# STM32.net
KiCad netlist of a schematic drawn in Altium Designer
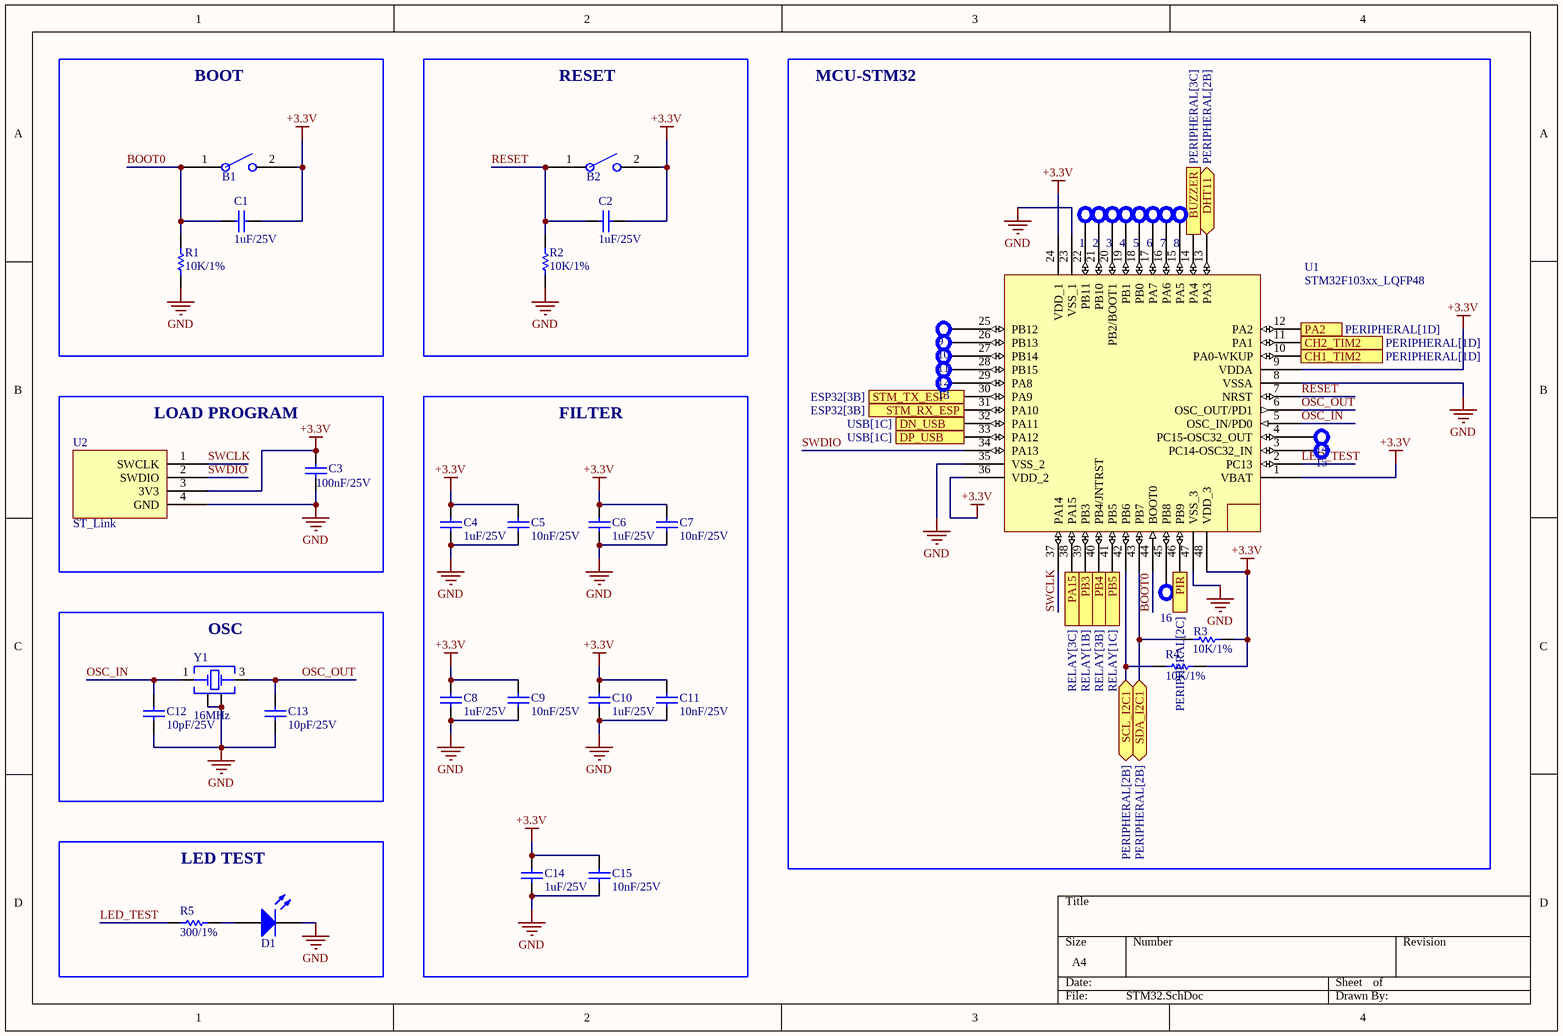
[diagram p0: STM32.SchDoc]

(export (version "E")
  (design (tool "Eeschema 10.0.6"))
  (components
    (comp (ref "1")
      (value "Test Point")
      (footprint "TP")
      (libsource (lib "Giang's Libs") (part "Test Point"))
    )
    (comp (ref "2")
      (value "Test Point")
      (footprint "TP")
      (libsource (lib "Giang's Libs") (part "Test Point"))
    )
    (comp (ref "3")
      (value "Test Point")
      (footprint "TP")
      (libsource (lib "Giang's Libs") (part "Test Point"))
    )
    (comp (ref "4")
      (value "Test Point")
      (footprint "TP")
      (libsource (lib "Giang's Libs") (part "Test Point"))
    )
    (comp (ref "5")
      (value "Test Point")
      (footprint "TP")
      (libsource (lib "Giang's Libs") (part "Test Point"))
    )
    (comp (ref "6")
      (value "Test Point")
      (footprint "TP")
      (libsource (lib "Giang's Libs") (part "Test Point"))
    )
    (comp (ref "7")
      (value "Test Point")
      (footprint "TP")
      (libsource (lib "Giang's Libs") (part "Test Point"))
    )
    (comp (ref "8")
      (value "Test Point")
      (footprint "TP")
      (libsource (lib "Giang's Libs") (part "Test Point"))
    )
    (comp (ref "9")
      (value "Test Point")
      (footprint "TP")
      (libsource (lib "Giang's Libs") (part "Test Point"))
    )
    (comp (ref "10")
      (value "Test Point")
      (footprint "TP")
      (libsource (lib "Giang's Libs") (part "Test Point"))
    )
    (comp (ref "11")
      (value "Test Point")
      (footprint "TP")
      (libsource (lib "Giang's Libs") (part "Test Point"))
    )
    (comp (ref "12")
      (value "Test Point")
      (footprint "TP")
      (libsource (lib "Giang's Libs") (part "Test Point"))
    )
    (comp (ref "13")
      (value "Test Point")
      (footprint "TP")
      (libsource (lib "Giang's Libs") (part "Test Point"))
    )
    (comp (ref "14")
      (value "Test Point")
      (footprint "TP")
      (libsource (lib "Giang's Libs") (part "Test Point"))
    )
    (comp (ref "15")
      (value "Test Point")
      (footprint "TP")
      (libsource (lib "Giang's Libs") (part "Test Point"))
    )
    (comp (ref "16")
      (value "Test Point")
      (footprint "TP")
      (libsource (lib "Giang's Libs") (part "Test Point"))
    )
    (comp (ref "B1")
      (value "Button SMD 2 Pin 3x4mm")
      (footprint "BUTTON SMD 2 PIN")
      (libsource (lib "Libs_NGOCCAM") (part "BUTTON"))
    )
    (comp (ref "B2")
      (value "Button SMD 2 Pin 3x4mm")
      (footprint "BUTTON SMD 2 PIN")
      (libsource (lib "Libs_NGOCCAM") (part "BUTTON"))
    )
    (comp (ref "C1")
      (value "1uF/25V")
      (footprint "CAP-SM-0805")
      (description "Capacitor")
      (fields (field (name "Comment") "Cap Non-Pol SMD"))
      (libsource (lib "PIF_Library") (part "Cap Non-Pol SMD"))
    )
    (comp (ref "C2")
      (value "1uF/25V")
      (footprint "CAP-SM-0805")
      (description "Capacitor")
      (fields (field (name "Comment") "Cap Non-Pol SMD"))
      (libsource (lib "PIF_Library") (part "Cap Non-Pol SMD"))
    )
    (comp (ref "C3")
      (value "100nF/25V")
      (footprint "CAP-SM-0805")
      (description "Capacitor")
      (fields (field (name "Comment") "Cap Non-Pol SMD"))
      (libsource (lib "PIF_Library") (part "Cap Non-Pol SMD"))
    )
    (comp (ref "C4")
      (value "1uF/25V")
      (footprint "CAP-SM-0805")
      (description "Capacitor")
      (fields (field (name "Comment") "Cap Non-Pol SMD"))
      (libsource (lib "PIF_Library") (part "Cap Non-Pol SMD"))
    )
    (comp (ref "C5")
      (value "10nF/25V")
      (footprint "CAP-SM-0805")
      (description "Capacitor")
      (fields (field (name "Comment") "Cap Non-Pol SMD"))
      (libsource (lib "PIF_Library") (part "Cap Non-Pol SMD"))
    )
    (comp (ref "C6")
      (value "1uF/25V")
      (footprint "CAP-SM-0805")
      (description "Capacitor")
      (fields (field (name "Comment") "Cap Non-Pol SMD"))
      (libsource (lib "PIF_Library") (part "Cap Non-Pol SMD"))
    )
    (comp (ref "C7")
      (value "10nF/25V")
      (footprint "CAP-SM-0805")
      (description "Capacitor")
      (fields (field (name "Comment") "Cap Non-Pol SMD"))
      (libsource (lib "PIF_Library") (part "Cap Non-Pol SMD"))
    )
    (comp (ref "C8")
      (value "1uF/25V")
      (footprint "CAP-SM-0805")
      (description "Capacitor")
      (fields (field (name "Comment") "Cap Non-Pol SMD"))
      (libsource (lib "PIF_Library") (part "Cap Non-Pol SMD"))
    )
    (comp (ref "C9")
      (value "10nF/25V")
      (footprint "CAP-SM-0805")
      (description "Capacitor")
      (fields (field (name "Comment") "Cap Non-Pol SMD"))
      (libsource (lib "PIF_Library") (part "Cap Non-Pol SMD"))
    )
    (comp (ref "C10")
      (value "1uF/25V")
      (footprint "CAP-SM-0805")
      (description "Capacitor")
      (fields (field (name "Comment") "Cap Non-Pol SMD"))
      (libsource (lib "PIF_Library") (part "Cap Non-Pol SMD"))
    )
    (comp (ref "C11")
      (value "10nF/25V")
      (footprint "CAP-SM-0805")
      (description "Capacitor")
      (fields (field (name "Comment") "Cap Non-Pol SMD"))
      (libsource (lib "PIF_Library") (part "Cap Non-Pol SMD"))
    )
    (comp (ref "C12")
      (value "10pF/25V")
      (footprint "CAP-SM-0805")
      (description "Capacitor")
      (fields (field (name "Comment") "Cap Non-Pol SMD"))
      (libsource (lib "PIF_Library") (part "Cap Non-Pol SMD"))
    )
    (comp (ref "C13")
      (value "10pF/25V")
      (footprint "CAP-SM-0805")
      (description "Capacitor")
      (fields (field (name "Comment") "Cap Non-Pol SMD"))
      (libsource (lib "PIF_Library") (part "Cap Non-Pol SMD"))
    )
    (comp (ref "C14")
      (value "1uF/25V")
      (footprint "CAP-SM-0805")
      (description "Capacitor")
      (fields (field (name "Comment") "Cap Non-Pol SMD"))
      (libsource (lib "PIF_Library") (part "Cap Non-Pol SMD"))
    )
    (comp (ref "C15")
      (value "10nF/25V")
      (footprint "CAP-SM-0805")
      (description "Capacitor")
      (fields (field (name "Comment") "Cap Non-Pol SMD"))
      (libsource (lib "PIF_Library") (part "Cap Non-Pol SMD"))
    )
    (comp (ref "D1")
      (value "LED SMD")
      (footprint "LED_0805_Blue")
      (description "LED")
      (libsource (lib "PIF_Library") (part "LED SMD"))
    )
    (comp (ref "R1")
      (value "10K/1%")
      (footprint "RES-SM-0805")
      (description "Resistor")
      (fields (field (name "Comment") "RESISTOR SMD"))
      (libsource (lib "PIF_Library") (part "RESISTOR SMD"))
    )
    (comp (ref "R2")
      (value "10K/1%")
      (footprint "RES-SM-0805")
      (description "Resistor")
      (fields (field (name "Comment") "RESISTOR SMD"))
      (libsource (lib "PIF_Library") (part "RESISTOR SMD"))
    )
    (comp (ref "R3")
      (value "10K/1%")
      (footprint "RES-SM-0805")
      (description "Resistor")
      (fields (field (name "Comment") "RESISTOR SMD"))
      (libsource (lib "PIF_Library") (part "RESISTOR SMD"))
    )
    (comp (ref "R4")
      (value "10K/1%")
      (footprint "RES-SM-0805")
      (description "Resistor")
      (fields (field (name "Comment") "RESISTOR SMD"))
      (libsource (lib "PIF_Library") (part "RESISTOR SMD"))
    )
    (comp (ref "R5")
      (value "300/1%")
      (footprint "RES-SM-0805")
      (description "Resistor")
      (fields (field (name "Comment") "RESISTOR SMD"))
      (libsource (lib "PIF_Library") (part "RESISTOR SMD"))
    )
    (comp (ref "U1")
      (value "STM32F103xx_LQFP48")
      (footprint "STM32_LQPF48")
      (fields (field (name "PUBLISHER") "Altium Limited"))
      (libsource (lib "Altium_Lib_by_KhueNguyenCreator") (part "STM32F103xx_LQFP48"))
    )
    (comp (ref "U2")
      (value "ST_Link")
      (footprint "Header 4 Pin")
      (libsource (lib "Schematic") (part "ST_Link"))
    )
    (comp (ref "Y1")
      (value "16MHz")
      (footprint "WE-XTAL_CFPX-180")
      (description "WE-XTAL Quartz Crystal, SMT, CFPX-180, 16MHz, +/-20ppm")
      (fields
        (field (name "MANUFACTURER PART NUMBER") "NX3225SA-16.000M-STD-CRS-2")
        (field (name "MANUFACTURER") "NDK")
      )
      (libsource (lib "Altium_XTAL") (part "073525166008"))
    )
  )
  (nets
    (net (code "1") (name "+3.3V") (class "Default")
      (node (ref "B1") (pin "2") (pintype "passive"))
      (node (ref "B2") (pin "2") (pintype "passive"))
      (node (ref "C1") (pin "2") (pinfunction "2_2") (pintype "passive"))
      (node (ref "C10") (pin "2") (pinfunction "2_2") (pintype "passive"))
      (node (ref "C11") (pin "2") (pinfunction "2_2") (pintype "passive"))
      (node (ref "C14") (pin "2") (pinfunction "2_2") (pintype "passive"))
      (node (ref "C15") (pin "2") (pinfunction "2_2") (pintype "passive"))
      (node (ref "C2") (pin "2") (pinfunction "2_2") (pintype "passive"))
      (node (ref "C3") (pin "2") (pinfunction "2_2") (pintype "passive"))
      (node (ref "C4") (pin "2") (pinfunction "2_2") (pintype "passive"))
      (node (ref "C5") (pin "2") (pinfunction "2_2") (pintype "passive"))
      (node (ref "C6") (pin "2") (pinfunction "2_2") (pintype "passive"))
      (node (ref "C7") (pin "2") (pinfunction "2_2") (pintype "passive"))
      (node (ref "C8") (pin "2") (pinfunction "2_2") (pintype "passive"))
      (node (ref "C9") (pin "2") (pinfunction "2_2") (pintype "passive"))
      (node (ref "R3") (pin "1") (pinfunction "1_1") (pintype "passive"))
      (node (ref "R4") (pin "1") (pinfunction "1_1") (pintype "passive"))
      (node (ref "U1") (pin "1") (pinfunction "VBAT_1") (pintype "power_in"))
      (node (ref "U1") (pin "24") (pinfunction "VDD_1_24") (pintype "power_in"))
      (node (ref "U1") (pin "36") (pinfunction "VDD_2_36") (pintype "power_in"))
      (node (ref "U1") (pin "48") (pinfunction "VDD_3_48") (pintype "power_in"))
      (node (ref "U1") (pin "9") (pinfunction "VDDA_9") (pintype "power_in"))
      (node (ref "U2") (pin "3") (pinfunction "3V3_3") (pintype "passive"))
    )
    (net (code "2") (name "/BOOT0") (class "Default")
      (node (ref "B1") (pin "1") (pintype "passive"))
      (node (ref "C1") (pin "1") (pinfunction "1_1") (pintype "passive"))
      (node (ref "R1") (pin "2") (pinfunction "2_2") (pintype "passive"))
      (node (ref "U1") (pin "44") (pinfunction "BOOT0_44") (pintype "input"))
    )
    (net (code "3") (name "/BUZZER") (class "Default")
      (node (ref "U1") (pin "14") (pinfunction "PA4_14") (pintype "bidirectional"))
    )
    (net (code "4") (name "/CH1_TIM2") (class "Default")
      (node (ref "U1") (pin "10") (pinfunction "PA0-WKUP_10") (pintype "bidirectional"))
    )
    (net (code "5") (name "/CH2_TIM2") (class "Default")
      (node (ref "U1") (pin "11") (pinfunction "PA1_11") (pintype "bidirectional"))
    )
    (net (code "6") (name "/DHT11") (class "Default")
      (node (ref "U1") (pin "13") (pinfunction "PA3_13") (pintype "bidirectional"))
    )
    (net (code "7") (name "/DN_USB") (class "Default")
      (node (ref "U1") (pin "32") (pinfunction "PA11_32") (pintype "bidirectional"))
    )
    (net (code "8") (name "/DP_USB") (class "Default")
      (node (ref "U1") (pin "33") (pinfunction "PA12_33") (pintype "bidirectional"))
    )
    (net (code "9") (name "/LED_TEST") (class "Default")
      (node (ref "R5") (pin "1") (pinfunction "1_1") (pintype "passive"))
      (node (ref "U1") (pin "2") (pinfunction "PC13_2") (pintype "bidirectional"))
    )
    (net (code "10") (name "/OSC_IN") (class "Default")
      (node (ref "C12") (pin "1") (pinfunction "1_1") (pintype "passive"))
      (node (ref "U1") (pin "5") (pinfunction "OSC_IN/PD0_5") (pintype "input"))
      (node (ref "Y1") (pin "1") (pinfunction "Crystal_1") (pintype "passive"))
    )
    (net (code "11") (name "/OSC_OUT") (class "Default")
      (node (ref "C13") (pin "1") (pinfunction "1_1") (pintype "passive"))
      (node (ref "U1") (pin "6") (pinfunction "OSC_OUT/PD1_6") (pintype "output"))
      (node (ref "Y1") (pin "3") (pinfunction "Crystal_3") (pintype "passive"))
    )
    (net (code "12") (name "/PA2") (class "Default")
      (node (ref "U1") (pin "12") (pinfunction "PA2_12") (pintype "bidirectional"))
    )
    (net (code "13") (name "/PA15") (class "Default")
      (node (ref "U1") (pin "38") (pinfunction "PA15_38") (pintype "bidirectional"))
    )
    (net (code "14") (name "/PB3") (class "Default")
      (node (ref "U1") (pin "39") (pinfunction "PB3_39") (pintype "bidirectional"))
    )
    (net (code "15") (name "/PB4") (class "Default")
      (node (ref "U1") (pin "40") (pinfunction "PB4/JNTRST_40") (pintype "bidirectional"))
    )
    (net (code "16") (name "/PB5") (class "Default")
      (node (ref "U1") (pin "41") (pinfunction "PB5_41") (pintype "bidirectional"))
    )
    (net (code "17") (name "/PIR") (class "Default")
      (node (ref "U1") (pin "46") (pinfunction "PB9_46") (pintype "bidirectional"))
    )
    (net (code "18") (name "/RESET") (class "Default")
      (node (ref "B2") (pin "1") (pintype "passive"))
      (node (ref "C2") (pin "1") (pinfunction "1_1") (pintype "passive"))
      (node (ref "R2") (pin "2") (pinfunction "2_2") (pintype "passive"))
      (node (ref "U1") (pin "7") (pinfunction "NRST_7") (pintype "bidirectional"))
    )
    (net (code "19") (name "/SCL_I2C1") (class "Default")
      (node (ref "R4") (pin "2") (pinfunction "2_2") (pintype "passive"))
      (node (ref "U1") (pin "42") (pinfunction "PB6_42") (pintype "bidirectional"))
    )
    (net (code "20") (name "/SDA_I2C1") (class "Default")
      (node (ref "R3") (pin "2") (pinfunction "2_2") (pintype "passive"))
      (node (ref "U1") (pin "43") (pinfunction "PB7_43") (pintype "bidirectional"))
    )
    (net (code "21") (name "/STM_RX_ESP") (class "Default")
      (node (ref "U1") (pin "31") (pinfunction "PA10_31") (pintype "bidirectional"))
    )
    (net (code "22") (name "/STM_TX_ESP") (class "Default")
      (node (ref "U1") (pin "30") (pinfunction "PA9_30") (pintype "bidirectional"))
    )
    (net (code "23") (name "/SWCLK") (class "Default")
      (node (ref "U1") (pin "37") (pinfunction "PA14_37") (pintype "bidirectional"))
      (node (ref "U2") (pin "1") (pinfunction "SWCLK_1") (pintype "passive"))
    )
    (net (code "24") (name "/SWDIO") (class "Default")
      (node (ref "U1") (pin "34") (pinfunction "PA13_34") (pintype "bidirectional"))
      (node (ref "U2") (pin "2") (pinfunction "SWDIO_2") (pintype "passive"))
    )
    (net (code "25") (name "GND") (class "Default")
      (node (ref "C10") (pin "1") (pinfunction "1_1") (pintype "passive"))
      (node (ref "C11") (pin "1") (pinfunction "1_1") (pintype "passive"))
      (node (ref "C12") (pin "2") (pinfunction "2_2") (pintype "passive"))
      (node (ref "C13") (pin "2") (pinfunction "2_2") (pintype "passive"))
      (node (ref "C14") (pin "1") (pinfunction "1_1") (pintype "passive"))
      (node (ref "C15") (pin "1") (pinfunction "1_1") (pintype "passive"))
      (node (ref "C3") (pin "1") (pinfunction "1_1") (pintype "passive"))
      (node (ref "C4") (pin "1") (pinfunction "1_1") (pintype "passive"))
      (node (ref "C5") (pin "1") (pinfunction "1_1") (pintype "passive"))
      (node (ref "C6") (pin "1") (pinfunction "1_1") (pintype "passive"))
      (node (ref "C7") (pin "1") (pinfunction "1_1") (pintype "passive"))
      (node (ref "C8") (pin "1") (pinfunction "1_1") (pintype "passive"))
      (node (ref "C9") (pin "1") (pinfunction "1_1") (pintype "passive"))
      (node (ref "D1") (pin "2") (pinfunction "K_2") (pintype "passive"))
      (node (ref "R1") (pin "1") (pinfunction "1_1") (pintype "passive"))
      (node (ref "R2") (pin "1") (pinfunction "1_1") (pintype "passive"))
      (node (ref "U1") (pin "23") (pinfunction "VSS_1_23") (pintype "power_in"))
      (node (ref "U1") (pin "35") (pinfunction "VSS_2_35") (pintype "power_in"))
      (node (ref "U1") (pin "47") (pinfunction "VSS_3_47") (pintype "power_in"))
      (node (ref "U1") (pin "8") (pinfunction "VSSA_8") (pintype "power_in"))
      (node (ref "U2") (pin "4") (pinfunction "GND_4") (pintype "passive"))
      (node (ref "Y1") (pin "2") (pinfunction "GND_2") (pintype "passive"))
      (node (ref "Y1") (pin "4") (pinfunction "GND_4") (pintype "passive"))
    )
    (net (code "26") (name "Net-(D1-A)") (class "Default")
      (node (ref "D1") (pin "1") (pinfunction "A_1") (pintype "passive"))
      (node (ref "R5") (pin "2") (pinfunction "2_2") (pintype "passive"))
    )
    (net (code "27") (name "Net-(U1-PA5)") (class "Default")
      (node (ref "8") (pin "1") (pinfunction "1_1") (pintype "passive"))
      (node (ref "U1") (pin "15") (pinfunction "PA5_15") (pintype "bidirectional"))
    )
    (net (code "28") (name "Net-(U1-PA6)") (class "Default")
      (node (ref "7") (pin "1") (pinfunction "1_1") (pintype "passive"))
      (node (ref "U1") (pin "16") (pinfunction "PA6_16") (pintype "bidirectional"))
    )
    (net (code "29") (name "Net-(U1-PA7)") (class "Default")
      (node (ref "6") (pin "1") (pinfunction "1_1") (pintype "passive"))
      (node (ref "U1") (pin "17") (pinfunction "PA7_17") (pintype "bidirectional"))
    )
    (net (code "30") (name "Net-(U1-PA8)") (class "Default")
      (node (ref "13") (pin "1") (pinfunction "1_1") (pintype "passive"))
      (node (ref "U1") (pin "29") (pinfunction "PA8_29") (pintype "bidirectional"))
    )
    (net (code "31") (name "Net-(U1-PB0)") (class "Default")
      (node (ref "5") (pin "1") (pinfunction "1_1") (pintype "passive"))
      (node (ref "U1") (pin "18") (pinfunction "PB0_18") (pintype "bidirectional"))
    )
    (net (code "32") (name "Net-(U1-PB1)") (class "Default")
      (node (ref "4") (pin "1") (pinfunction "1_1") (pintype "passive"))
      (node (ref "U1") (pin "19") (pinfunction "PB1_19") (pintype "bidirectional"))
    )
    (net (code "33") (name "Net-(U1-PB2{slash}BOOT1)") (class "Default")
      (node (ref "3") (pin "1") (pinfunction "1_1") (pintype "passive"))
      (node (ref "U1") (pin "20") (pinfunction "PB2/BOOT1_20") (pintype "bidirectional"))
    )
    (net (code "34") (name "Net-(U1-PB8)") (class "Default")
      (node (ref "16") (pin "1") (pinfunction "1_1") (pintype "passive"))
      (node (ref "U1") (pin "45") (pinfunction "PB8_45") (pintype "bidirectional"))
    )
    (net (code "35") (name "Net-(U1-PB10)") (class "Default")
      (node (ref "2") (pin "1") (pinfunction "1_1") (pintype "passive"))
      (node (ref "U1") (pin "21") (pinfunction "PB10_21") (pintype "bidirectional"))
    )
    (net (code "36") (name "Net-(U1-PB11)") (class "Default")
      (node (ref "1") (pin "1") (pinfunction "1_1") (pintype "passive"))
      (node (ref "U1") (pin "22") (pinfunction "PB11_22") (pintype "bidirectional"))
    )
    (net (code "37") (name "Net-(U1-PB12)") (class "Default")
      (node (ref "9") (pin "1") (pinfunction "1_1") (pintype "passive"))
      (node (ref "U1") (pin "25") (pinfunction "PB12_25") (pintype "bidirectional"))
    )
    (net (code "38") (name "Net-(U1-PB13)") (class "Default")
      (node (ref "10") (pin "1") (pinfunction "1_1") (pintype "passive"))
      (node (ref "U1") (pin "26") (pinfunction "PB13_26") (pintype "bidirectional"))
    )
    (net (code "39") (name "Net-(U1-PB14)") (class "Default")
      (node (ref "11") (pin "1") (pinfunction "1_1") (pintype "passive"))
      (node (ref "U1") (pin "27") (pinfunction "PB14_27") (pintype "bidirectional"))
    )
    (net (code "40") (name "Net-(U1-PB15)") (class "Default")
      (node (ref "12") (pin "1") (pinfunction "1_1") (pintype "passive"))
      (node (ref "U1") (pin "28") (pinfunction "PB15_28") (pintype "bidirectional"))
    )
    (net (code "41") (name "Net-(U1-PC14-OSC32_IN)") (class "Default")
      (node (ref "15") (pin "1") (pinfunction "1_1") (pintype "passive"))
      (node (ref "U1") (pin "3") (pinfunction "PC14-OSC32_IN_3") (pintype "bidirectional"))
    )
    (net (code "42") (name "Net-(U1-PC15-OSC32_OUT)") (class "Default")
      (node (ref "14") (pin "1") (pinfunction "1_1") (pintype "passive"))
      (node (ref "U1") (pin "4") (pinfunction "PC15-OSC32_OUT_4") (pintype "bidirectional"))
    )
  )
)
